# AIR.net
KiCad netlist of a schematic drawn in EAGLE
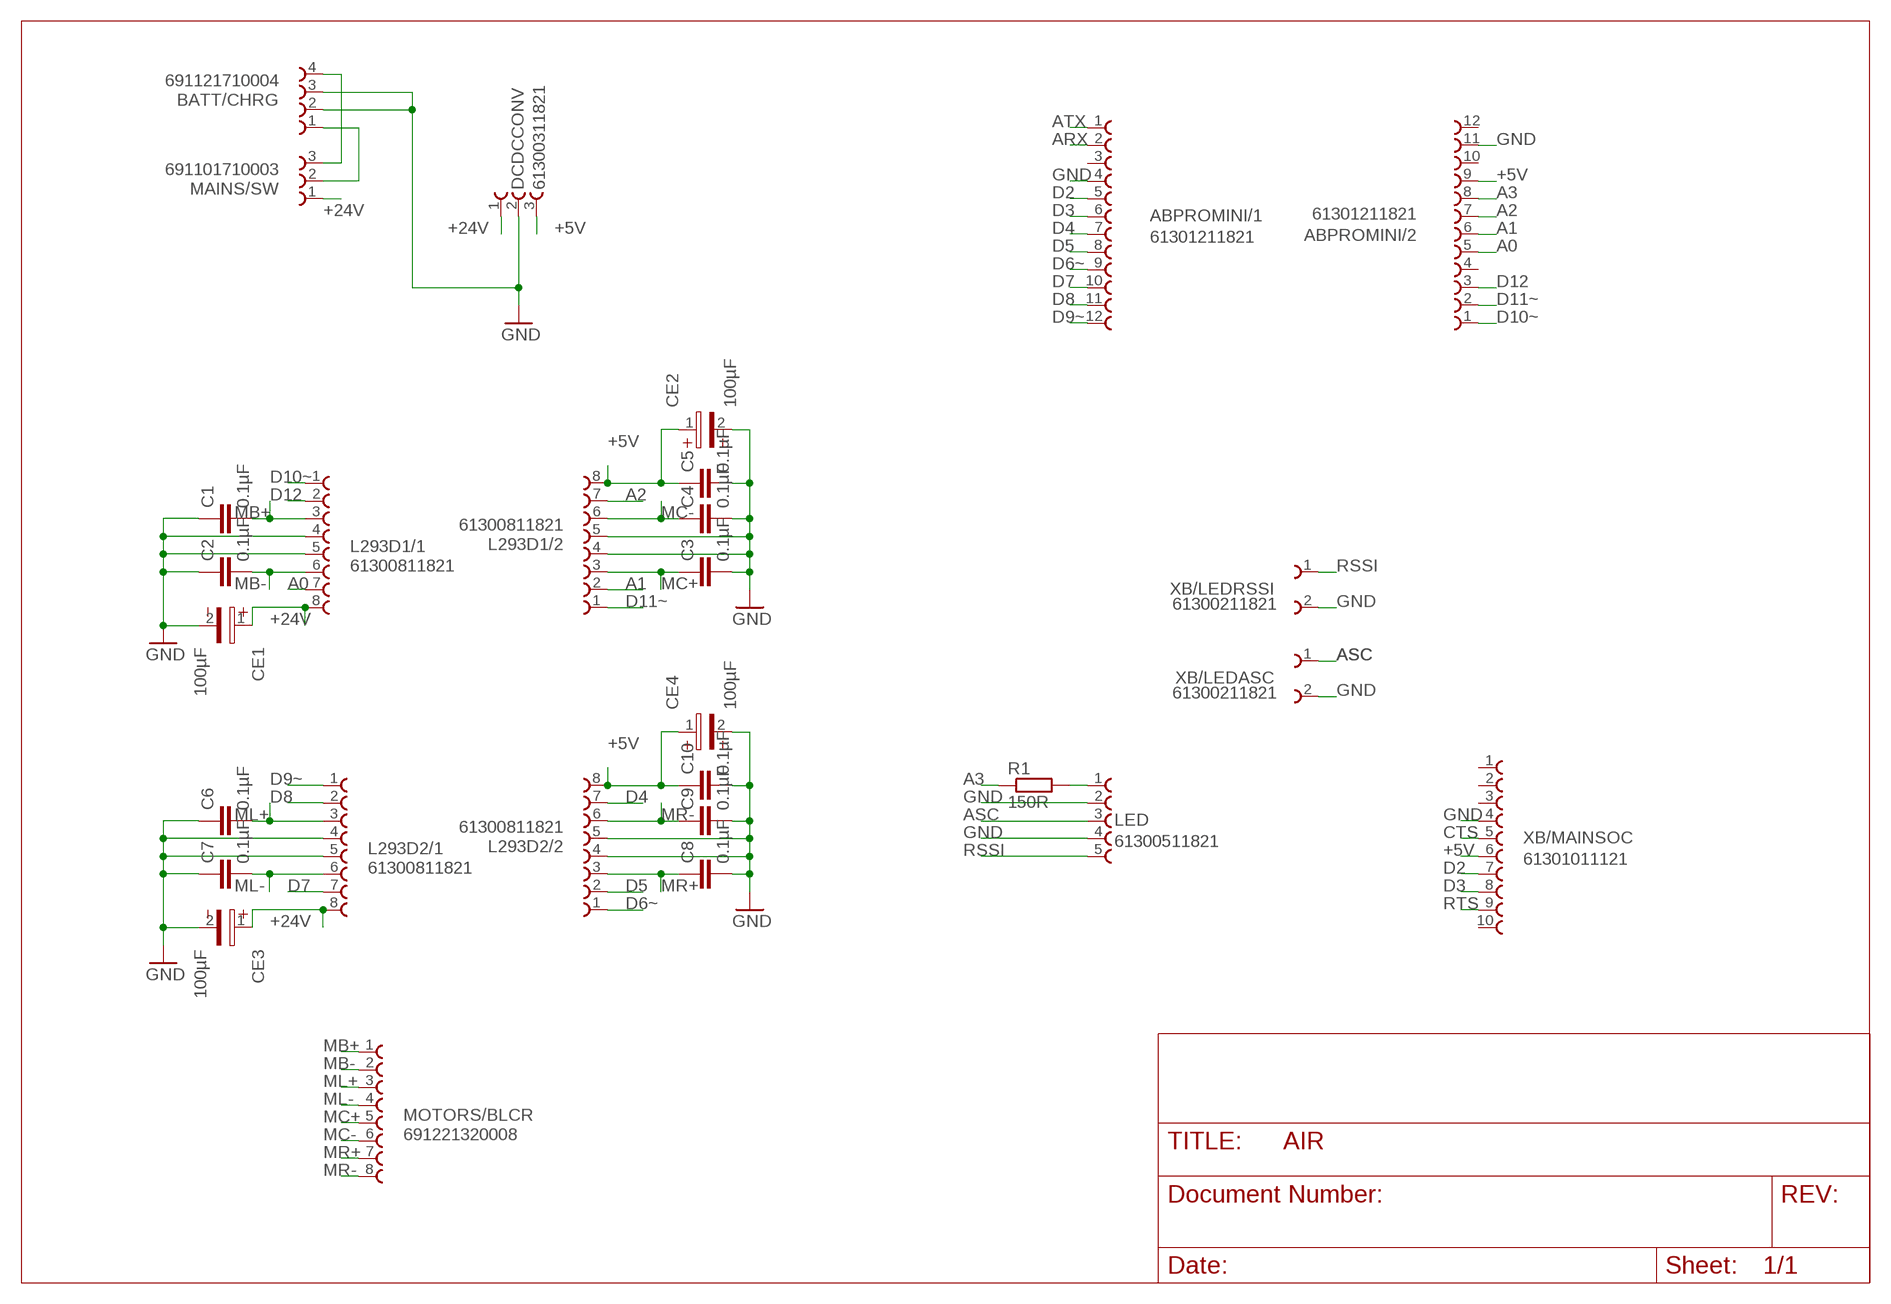
[diagram p0: schematic, sheet 1]

(export (version "E")
  (design (tool "Eeschema 10.0.6"))
  (components
    (comp (ref "ABPROMINI/1")
      (value "61301211821")
      (footprint "eagle-import:61301211821")
      (libsource (lib "eagle-import") (part "61301211821"))
    )
    (comp (ref "ABPROMINI/2")
      (value "61301211821")
      (footprint "eagle-import:61301211821")
      (libsource (lib "eagle-import") (part "61301211821"))
    )
    (comp (ref "BATT/CHRG")
      (value "691121710004")
      (footprint "eagle-import:691121710004")
      (libsource (lib "eagle-import") (part "691121710004"))
    )
    (comp (ref "C1")
      (value "0.1µF")
      (footprint "eagle-import:C025-025X050")
      (libsource (lib "eagle-import") (part "C-EU025-025X050"))
    )
    (comp (ref "C2")
      (value "0.1µF")
      (footprint "eagle-import:C025-025X050")
      (libsource (lib "eagle-import") (part "C-EU025-025X050"))
    )
    (comp (ref "C3")
      (value "0.1µF")
      (footprint "eagle-import:C025-025X050")
      (libsource (lib "eagle-import") (part "C-EU025-025X050"))
    )
    (comp (ref "C4")
      (value "0.1µF")
      (footprint "eagle-import:C025-025X050")
      (libsource (lib "eagle-import") (part "C-EU025-025X050"))
    )
    (comp (ref "C5")
      (value "0.1µF")
      (footprint "eagle-import:C025-025X050")
      (libsource (lib "eagle-import") (part "C-EU025-025X050"))
    )
    (comp (ref "C6")
      (value "0.1µF")
      (footprint "eagle-import:C025-025X050")
      (libsource (lib "eagle-import") (part "C-EU025-025X050"))
    )
    (comp (ref "C7")
      (value "0.1µF")
      (footprint "eagle-import:C025-025X050")
      (libsource (lib "eagle-import") (part "C-EU025-025X050"))
    )
    (comp (ref "C8")
      (value "0.1µF")
      (footprint "eagle-import:C025-025X050")
      (libsource (lib "eagle-import") (part "C-EU025-025X050"))
    )
    (comp (ref "C9")
      (value "0.1µF")
      (footprint "eagle-import:C025-025X050")
      (libsource (lib "eagle-import") (part "C-EU025-025X050"))
    )
    (comp (ref "C10")
      (value "0.1µF")
      (footprint "eagle-import:C025-025X050")
      (libsource (lib "eagle-import") (part "C-EU025-025X050"))
    )
    (comp (ref "CE1")
      (value "100µF")
      (footprint "eagle-import:8X3.5X0.9(DXAXB)")
      (libsource (lib "eagle-import") (part "WCAP-PTG5_8X8X3.5X0.6(DXLXPXØ)"))
    )
    (comp (ref "CE2")
      (value "100µF")
      (footprint "eagle-import:8X3.5X0.9(DXAXB)")
      (libsource (lib "eagle-import") (part "WCAP-PTG5_8X8X3.5X0.6(DXLXPXØ)"))
    )
    (comp (ref "CE3")
      (value "100µF")
      (footprint "eagle-import:8X3.5X0.9(DXAXB)")
      (libsource (lib "eagle-import") (part "WCAP-PTG5_8X8X3.5X0.6(DXLXPXØ)"))
    )
    (comp (ref "CE4")
      (value "100µF")
      (footprint "eagle-import:8X3.5X0.9(DXAXB)")
      (libsource (lib "eagle-import") (part "WCAP-PTG5_8X8X3.5X0.6(DXLXPXØ)"))
    )
    (comp (ref "DCDCCONV")
      (value "61300311821")
      (footprint "eagle-import:61300311821")
      (libsource (lib "eagle-import") (part "61300311821"))
    )
    (comp (ref "L293D1/1")
      (value "61300811821")
      (footprint "eagle-import:61300811821")
      (libsource (lib "eagle-import") (part "61300811821"))
    )
    (comp (ref "L293D1/2")
      (value "61300811821")
      (footprint "eagle-import:61300811821")
      (libsource (lib "eagle-import") (part "61300811821"))
    )
    (comp (ref "L293D2/1")
      (value "61300811821")
      (footprint "eagle-import:61300811821")
      (libsource (lib "eagle-import") (part "61300811821"))
    )
    (comp (ref "L293D2/2")
      (value "61300811821")
      (footprint "eagle-import:61300811821")
      (libsource (lib "eagle-import") (part "61300811821"))
    )
    (comp (ref "LED")
      (value "61300511821")
      (footprint "eagle-import:61300511821")
      (libsource (lib "eagle-import") (part "61300511821"))
    )
    (comp (ref "MAINS/SW")
      (value "691101710003")
      (footprint "eagle-import:691101710003")
      (libsource (lib "eagle-import") (part "691101710003"))
    )
    (comp (ref "MOTORS/BLCR")
      (value "691221320008")
      (footprint "eagle-import:691221320008")
      (libsource (lib "eagle-import") (part "691221320008"))
    )
    (comp (ref "R1")
      (value "150R")
      (footprint "eagle-import:0204_7")
      (libsource (lib "eagle-import") (part "R-EU_0204/7"))
    )
    (comp (ref "XB/LEDASC")
      (value "61300211821")
      (footprint "eagle-import:61300211821")
      (libsource (lib "eagle-import") (part "61300211821"))
    )
    (comp (ref "XB/LEDRSSI")
      (value "61300211821")
      (footprint "eagle-import:61300211821")
      (libsource (lib "eagle-import") (part "61300211821"))
    )
    (comp (ref "XB/MAINSOC")
      (value "61301011121")
      (footprint "eagle-import:61301011121")
      (libsource (lib "eagle-import") (part "61301011121"))
    )
  )
  (nets
    (net (code "1") (name "/+5V") (class "Default")
      (node (ref "ABPROMINI/2") (pin "9") (pinfunction "9_9") (pintype "passive"))
      (node (ref "C10") (pin "1") (pinfunction "1_1") (pintype "passive"))
      (node (ref "C5") (pin "1") (pinfunction "1_1") (pintype "passive"))
      (node (ref "CE2") (pin "1") (pinfunction "1_1") (pintype "bidirectional"))
      (node (ref "CE4") (pin "1") (pinfunction "1_1") (pintype "bidirectional"))
      (node (ref "DCDCCONV") (pin "3") (pinfunction "3_3") (pintype "passive"))
      (node (ref "L293D1/2") (pin "8") (pinfunction "8_8") (pintype "passive"))
      (node (ref "L293D2/2") (pin "8") (pinfunction "8_8") (pintype "passive"))
      (node (ref "XB/MAINSOC") (pin "6") (pinfunction "6_6") (pintype "passive"))
    )
    (net (code "2") (name "/+24V") (class "Default")
      (node (ref "CE1") (pin "1") (pinfunction "1_1") (pintype "bidirectional"))
      (node (ref "CE3") (pin "1") (pinfunction "1_1") (pintype "bidirectional"))
      (node (ref "DCDCCONV") (pin "1") (pinfunction "1_1") (pintype "passive"))
      (node (ref "L293D1/1") (pin "8") (pinfunction "8_8") (pintype "passive"))
      (node (ref "L293D2/1") (pin "8") (pinfunction "8_8") (pintype "passive"))
      (node (ref "MAINS/SW") (pin "1") (pinfunction "1_1") (pintype "passive"))
    )
    (net (code "3") (name "/A0") (class "Default")
      (node (ref "ABPROMINI/2") (pin "5") (pinfunction "5_5") (pintype "passive"))
      (node (ref "L293D1/1") (pin "7") (pinfunction "7_7") (pintype "passive"))
    )
    (net (code "4") (name "/A1") (class "Default")
      (node (ref "ABPROMINI/2") (pin "6") (pinfunction "6_6") (pintype "passive"))
      (node (ref "L293D1/2") (pin "2") (pinfunction "2_2") (pintype "passive"))
    )
    (net (code "5") (name "/A2") (class "Default")
      (node (ref "ABPROMINI/2") (pin "7") (pinfunction "7_7") (pintype "passive"))
      (node (ref "L293D1/2") (pin "7") (pinfunction "7_7") (pintype "passive"))
    )
    (net (code "6") (name "/A3") (class "Default")
      (node (ref "ABPROMINI/2") (pin "8") (pinfunction "8_8") (pintype "passive"))
      (node (ref "R1") (pin "1") (pinfunction "1_1") (pintype "passive"))
    )
    (net (code "7") (name "/ARX") (class "Default")
      (node (ref "ABPROMINI/1") (pin "2") (pinfunction "2_2") (pintype "passive"))
    )
    (net (code "8") (name "/ASC") (class "Default")
      (node (ref "LED") (pin "3") (pinfunction "3_3") (pintype "passive"))
      (node (ref "XB/LEDASC") (pin "1") (pinfunction "1_1") (pintype "passive"))
    )
    (net (code "9") (name "/ATX") (class "Default")
      (node (ref "ABPROMINI/1") (pin "1") (pinfunction "1_1") (pintype "passive"))
    )
    (net (code "10") (name "/CTS") (class "Default")
      (node (ref "XB/MAINSOC") (pin "5") (pinfunction "5_5") (pintype "passive"))
    )
    (net (code "11") (name "/D2") (class "Default")
      (node (ref "ABPROMINI/1") (pin "5") (pinfunction "5_5") (pintype "passive"))
      (node (ref "XB/MAINSOC") (pin "7") (pinfunction "7_7") (pintype "passive"))
    )
    (net (code "12") (name "/D3") (class "Default")
      (node (ref "ABPROMINI/1") (pin "6") (pinfunction "6_6") (pintype "passive"))
      (node (ref "XB/MAINSOC") (pin "8") (pinfunction "8_8") (pintype "passive"))
    )
    (net (code "13") (name "/D4") (class "Default")
      (node (ref "ABPROMINI/1") (pin "7") (pinfunction "7_7") (pintype "passive"))
      (node (ref "L293D2/2") (pin "7") (pinfunction "7_7") (pintype "passive"))
    )
    (net (code "14") (name "/D5") (class "Default")
      (node (ref "ABPROMINI/1") (pin "8") (pinfunction "8_8") (pintype "passive"))
      (node (ref "L293D2/2") (pin "2") (pinfunction "2_2") (pintype "passive"))
    )
    (net (code "15") (name "/D6~{}") (class "Default")
      (node (ref "ABPROMINI/1") (pin "9") (pinfunction "9_9") (pintype "passive"))
      (node (ref "L293D2/2") (pin "1") (pinfunction "1_1") (pintype "passive"))
    )
    (net (code "16") (name "/D7") (class "Default")
      (node (ref "ABPROMINI/1") (pin "10") (pinfunction "10_10") (pintype "passive"))
      (node (ref "L293D2/1") (pin "7") (pinfunction "7_7") (pintype "passive"))
    )
    (net (code "17") (name "/D8") (class "Default")
      (node (ref "ABPROMINI/1") (pin "11") (pinfunction "11_11") (pintype "passive"))
      (node (ref "L293D2/1") (pin "2") (pinfunction "2_2") (pintype "passive"))
    )
    (net (code "18") (name "/D9~{}") (class "Default")
      (node (ref "ABPROMINI/1") (pin "12") (pinfunction "12_12") (pintype "passive"))
      (node (ref "L293D2/1") (pin "1") (pinfunction "1_1") (pintype "passive"))
    )
    (net (code "19") (name "/D10~{}") (class "Default")
      (node (ref "ABPROMINI/2") (pin "1") (pinfunction "1_1") (pintype "passive"))
      (node (ref "L293D1/1") (pin "1") (pinfunction "1_1") (pintype "passive"))
    )
    (net (code "20") (name "/D11~{}") (class "Default")
      (node (ref "ABPROMINI/2") (pin "2") (pinfunction "2_2") (pintype "passive"))
      (node (ref "L293D1/2") (pin "1") (pinfunction "1_1") (pintype "passive"))
    )
    (net (code "21") (name "/D12") (class "Default")
      (node (ref "ABPROMINI/2") (pin "3") (pinfunction "3_3") (pintype "passive"))
      (node (ref "L293D1/1") (pin "2") (pinfunction "2_2") (pintype "passive"))
    )
    (net (code "22") (name "/MB+") (class "Default")
      (node (ref "C1") (pin "2") (pinfunction "2_2") (pintype "passive"))
      (node (ref "L293D1/1") (pin "3") (pinfunction "3_3") (pintype "passive"))
      (node (ref "MOTORS/BLCR") (pin "1") (pinfunction "1_1") (pintype "passive"))
    )
    (net (code "23") (name "/MB-") (class "Default")
      (node (ref "C2") (pin "2") (pinfunction "2_2") (pintype "passive"))
      (node (ref "L293D1/1") (pin "6") (pinfunction "6_6") (pintype "passive"))
      (node (ref "MOTORS/BLCR") (pin "2") (pinfunction "2_2") (pintype "passive"))
    )
    (net (code "24") (name "/MC+") (class "Default")
      (node (ref "C3") (pin "1") (pinfunction "1_1") (pintype "passive"))
      (node (ref "L293D1/2") (pin "3") (pinfunction "3_3") (pintype "passive"))
      (node (ref "MOTORS/BLCR") (pin "5") (pinfunction "5_5") (pintype "passive"))
    )
    (net (code "25") (name "/MC-") (class "Default")
      (node (ref "C4") (pin "1") (pinfunction "1_1") (pintype "passive"))
      (node (ref "L293D1/2") (pin "6") (pinfunction "6_6") (pintype "passive"))
      (node (ref "MOTORS/BLCR") (pin "6") (pinfunction "6_6") (pintype "passive"))
    )
    (net (code "26") (name "/ML+") (class "Default")
      (node (ref "C6") (pin "2") (pinfunction "2_2") (pintype "passive"))
      (node (ref "L293D2/1") (pin "3") (pinfunction "3_3") (pintype "passive"))
      (node (ref "MOTORS/BLCR") (pin "3") (pinfunction "3_3") (pintype "passive"))
    )
    (net (code "27") (name "/ML-") (class "Default")
      (node (ref "C7") (pin "2") (pinfunction "2_2") (pintype "passive"))
      (node (ref "L293D2/1") (pin "6") (pinfunction "6_6") (pintype "passive"))
      (node (ref "MOTORS/BLCR") (pin "4") (pinfunction "4_4") (pintype "passive"))
    )
    (net (code "28") (name "/MR+") (class "Default")
      (node (ref "C8") (pin "1") (pinfunction "1_1") (pintype "passive"))
      (node (ref "L293D2/2") (pin "3") (pinfunction "3_3") (pintype "passive"))
      (node (ref "MOTORS/BLCR") (pin "7") (pinfunction "7_7") (pintype "passive"))
    )
    (net (code "29") (name "/MR-") (class "Default")
      (node (ref "C9") (pin "1") (pinfunction "1_1") (pintype "passive"))
      (node (ref "L293D2/2") (pin "6") (pinfunction "6_6") (pintype "passive"))
      (node (ref "MOTORS/BLCR") (pin "8") (pinfunction "8_8") (pintype "passive"))
    )
    (net (code "30") (name "/RSSI") (class "Default")
      (node (ref "LED") (pin "5") (pinfunction "5_5") (pintype "passive"))
      (node (ref "XB/LEDRSSI") (pin "1") (pinfunction "1_1") (pintype "passive"))
    )
    (net (code "31") (name "/RTS") (class "Default")
      (node (ref "XB/MAINSOC") (pin "9") (pinfunction "9_9") (pintype "passive"))
    )
    (net (code "32") (name "GND") (class "Default")
      (node (ref "ABPROMINI/1") (pin "4") (pinfunction "4_4") (pintype "passive"))
      (node (ref "ABPROMINI/2") (pin "11") (pinfunction "11_11") (pintype "passive"))
      (node (ref "BATT/CHRG") (pin "2") (pinfunction "2_2") (pintype "passive"))
      (node (ref "BATT/CHRG") (pin "3") (pinfunction "3_3") (pintype "passive"))
      (node (ref "C1") (pin "1") (pinfunction "1_1") (pintype "passive"))
      (node (ref "C10") (pin "2") (pinfunction "2_2") (pintype "passive"))
      (node (ref "C2") (pin "1") (pinfunction "1_1") (pintype "passive"))
      (node (ref "C3") (pin "2") (pinfunction "2_2") (pintype "passive"))
      (node (ref "C4") (pin "2") (pinfunction "2_2") (pintype "passive"))
      (node (ref "C5") (pin "2") (pinfunction "2_2") (pintype "passive"))
      (node (ref "C6") (pin "1") (pinfunction "1_1") (pintype "passive"))
      (node (ref "C7") (pin "1") (pinfunction "1_1") (pintype "passive"))
      (node (ref "C8") (pin "2") (pinfunction "2_2") (pintype "passive"))
      (node (ref "C9") (pin "2") (pinfunction "2_2") (pintype "passive"))
      (node (ref "CE1") (pin "2") (pinfunction "2_2") (pintype "bidirectional"))
      (node (ref "CE2") (pin "2") (pinfunction "2_2") (pintype "bidirectional"))
      (node (ref "CE3") (pin "2") (pinfunction "2_2") (pintype "bidirectional"))
      (node (ref "CE4") (pin "2") (pinfunction "2_2") (pintype "bidirectional"))
      (node (ref "DCDCCONV") (pin "2") (pinfunction "2_2") (pintype "passive"))
      (node (ref "L293D1/1") (pin "4") (pinfunction "4_4") (pintype "passive"))
      (node (ref "L293D1/1") (pin "5") (pinfunction "5_5") (pintype "passive"))
      (node (ref "L293D1/2") (pin "4") (pinfunction "4_4") (pintype "passive"))
      (node (ref "L293D1/2") (pin "5") (pinfunction "5_5") (pintype "passive"))
      (node (ref "L293D2/1") (pin "4") (pinfunction "4_4") (pintype "passive"))
      (node (ref "L293D2/1") (pin "5") (pinfunction "5_5") (pintype "passive"))
      (node (ref "L293D2/2") (pin "4") (pinfunction "4_4") (pintype "passive"))
      (node (ref "L293D2/2") (pin "5") (pinfunction "5_5") (pintype "passive"))
      (node (ref "LED") (pin "2") (pinfunction "2_2") (pintype "passive"))
      (node (ref "LED") (pin "4") (pinfunction "4_4") (pintype "passive"))
      (node (ref "XB/LEDASC") (pin "2") (pinfunction "2_2") (pintype "passive"))
      (node (ref "XB/LEDRSSI") (pin "2") (pinfunction "2_2") (pintype "passive"))
      (node (ref "XB/MAINSOC") (pin "4") (pinfunction "4_4") (pintype "passive"))
    )
    (net (code "33") (name "Net-(BATT/CHRG-Pad1)") (class "Default")
      (node (ref "BATT/CHRG") (pin "1") (pinfunction "1_1") (pintype "passive"))
      (node (ref "MAINS/SW") (pin "2") (pinfunction "2_2") (pintype "passive"))
    )
    (net (code "34") (name "Net-(BATT/CHRG-Pad4)") (class "Default")
      (node (ref "BATT/CHRG") (pin "4") (pinfunction "4_4") (pintype "passive"))
      (node (ref "MAINS/SW") (pin "3") (pinfunction "3_3") (pintype "passive"))
    )
    (net (code "35") (name "Net-(LED-Pad1)") (class "Default")
      (node (ref "LED") (pin "1") (pinfunction "1_1") (pintype "passive"))
      (node (ref "R1") (pin "2") (pinfunction "2_2") (pintype "passive"))
    )
    (net (code "36") (name "unconnected-(ABPROMINI/1-Pad3)") (class "Default")
      (node (ref "ABPROMINI/1") (pin "3") (pinfunction "3_3") (pintype "passive"))
    )
    (net (code "37") (name "unconnected-(ABPROMINI/2-Pad4)") (class "Default")
      (node (ref "ABPROMINI/2") (pin "4") (pinfunction "4_4") (pintype "passive"))
    )
    (net (code "38") (name "unconnected-(ABPROMINI/2-Pad10)") (class "Default")
      (node (ref "ABPROMINI/2") (pin "10") (pinfunction "10_10") (pintype "passive"))
    )
    (net (code "39") (name "unconnected-(ABPROMINI/2-Pad12)") (class "Default")
      (node (ref "ABPROMINI/2") (pin "12") (pinfunction "12_12") (pintype "passive"))
    )
    (net (code "40") (name "unconnected-(XB/MAINSOC-Pad1)") (class "Default")
      (node (ref "XB/MAINSOC") (pin "1") (pinfunction "1_1") (pintype "passive"))
    )
    (net (code "41") (name "unconnected-(XB/MAINSOC-Pad2)") (class "Default")
      (node (ref "XB/MAINSOC") (pin "2") (pinfunction "2_2") (pintype "passive"))
    )
    (net (code "42") (name "unconnected-(XB/MAINSOC-Pad3)") (class "Default")
      (node (ref "XB/MAINSOC") (pin "3") (pinfunction "3_3") (pintype "passive"))
    )
    (net (code "43") (name "unconnected-(XB/MAINSOC-Pad10)") (class "Default")
      (node (ref "XB/MAINSOC") (pin "10") (pinfunction "10_10") (pintype "passive"))
    )
  )
)
